# V4-AddOnZigbee-DIL-V001.net
KiCad netlist of a schematic drawn in EAGLE
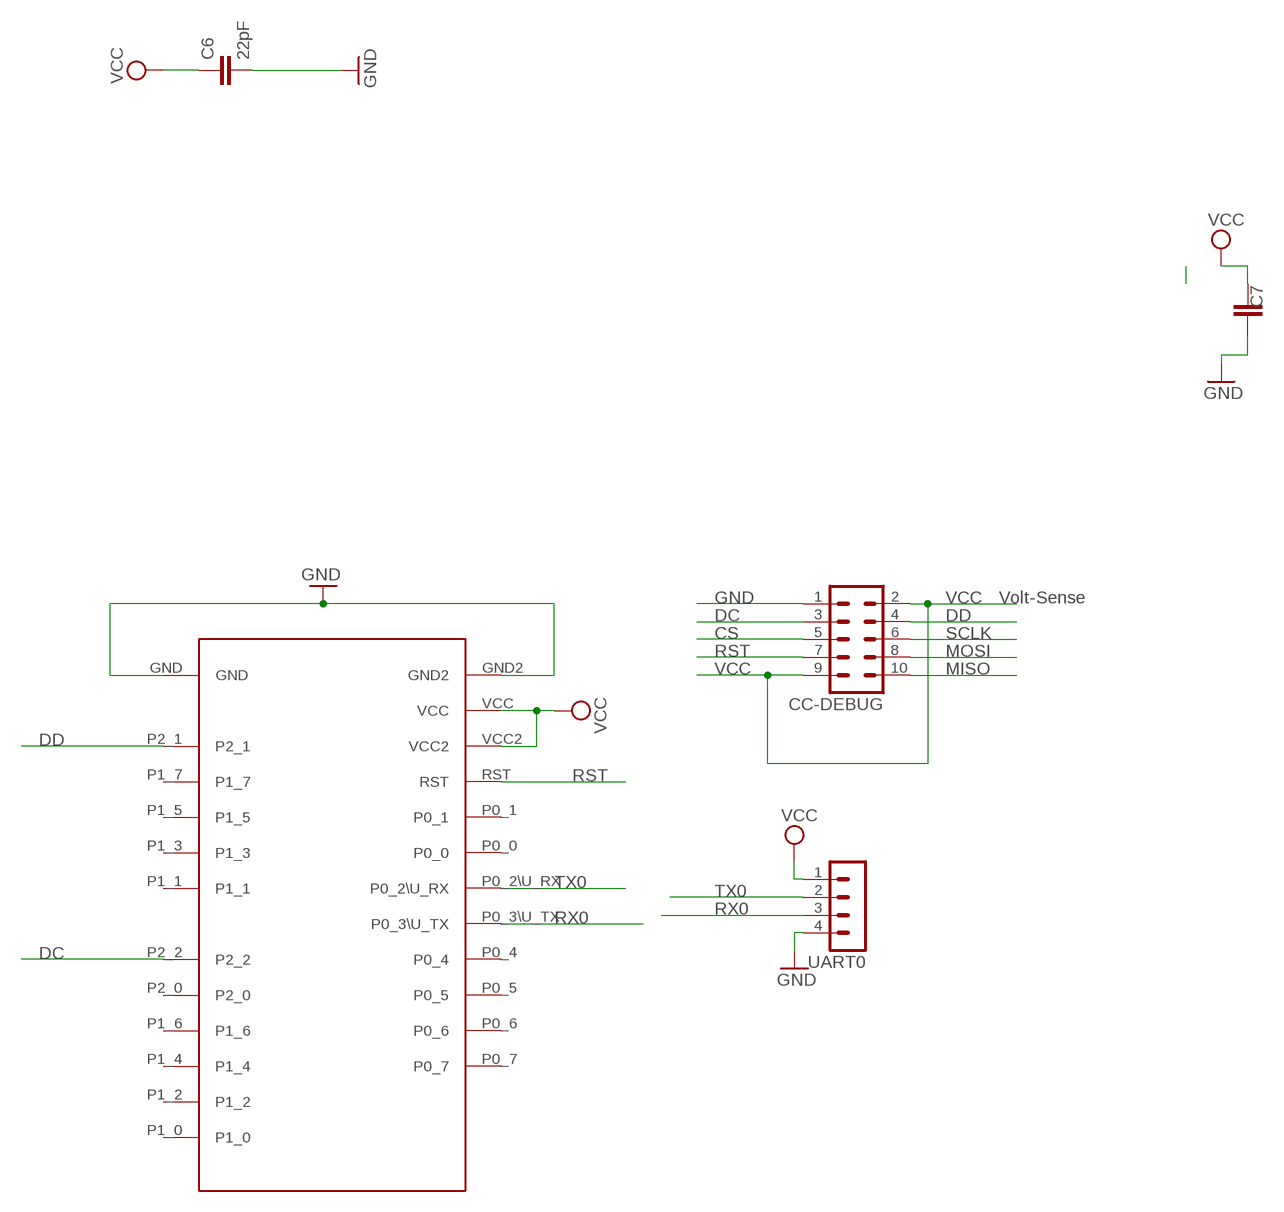
[diagram p0: schematic, sheet 1]

(export (version "E")
  (design (tool "Eeschema 10.0.6"))
  (components
    (comp (ref "C6")
      (value "22pF")
      (footprint "eagle-import:C0805")
      (libsource (lib "eagle-import") (part "C-EUC0805"))
    )
    (comp (ref "C7")
      (value "C-EUC1812")
      (footprint "eagle-import:C1812")
      (libsource (lib "eagle-import") (part "C-EUC1812"))
    )
    (comp (ref "CC-DEBUG")
      (value "MA05-2")
      (footprint "eagle-import:MA05-2")
      (libsource (lib "eagle-import") (part "MA05-2"))
    )
    (comp (ref "U$3")
      (value "CC2530_MODULE")
      (footprint "eagle-import:CC2530_DIL")
      (libsource (lib "eagle-import") (part "CC2530_MODULE"))
    )
    (comp (ref "UART0")
      (value "MA04-1")
      (footprint "eagle-import:MA04-1")
      (libsource (lib "eagle-import") (part "MA04-1"))
    )
  )
  (nets
    (net (code "1") (name "/CS") (class "Default")
      (node (ref "CC-DEBUG") (pin "5") (pinfunction "5_5") (pintype "passive"))
    )
    (net (code "2") (name "/DC") (class "Default")
      (node (ref "CC-DEBUG") (pin "3") (pinfunction "3_3") (pintype "passive"))
      (node (ref "U$3") (pin "P2_2") (pinfunction "P2_2_P2_2") (pintype "bidirectional"))
    )
    (net (code "3") (name "/DD") (class "Default")
      (node (ref "CC-DEBUG") (pin "4") (pinfunction "4_4") (pintype "passive"))
      (node (ref "U$3") (pin "P2_1") (pinfunction "P2_1_P2_1") (pintype "bidirectional"))
    )
    (net (code "4") (name "/MISO") (class "Default")
      (node (ref "CC-DEBUG") (pin "10") (pinfunction "10_10") (pintype "passive"))
    )
    (net (code "5") (name "/MOSI") (class "Default")
      (node (ref "CC-DEBUG") (pin "8") (pinfunction "8_8") (pintype "passive"))
    )
    (net (code "6") (name "/RST") (class "Default")
      (node (ref "CC-DEBUG") (pin "7") (pinfunction "7_7") (pintype "passive"))
      (node (ref "U$3") (pin "RST") (pinfunction "RST_RST") (pintype "bidirectional"))
    )
    (net (code "7") (name "/RX0") (class "Default")
      (node (ref "U$3") (pin "P0_3\\U_TX") (pinfunction "P0_3\\U_TX_P0_3\\U_TX") (pintype "bidirectional"))
      (node (ref "UART0") (pin "3") (pinfunction "3_3") (pintype "passive"))
    )
    (net (code "8") (name "/SCLK") (class "Default")
      (node (ref "CC-DEBUG") (pin "6") (pinfunction "6_6") (pintype "passive"))
    )
    (net (code "9") (name "/TX0") (class "Default")
      (node (ref "U$3") (pin "P0_2\\U_RX") (pinfunction "P0_2\\U_RX_P0_2\\U_RX") (pintype "bidirectional"))
      (node (ref "UART0") (pin "2") (pinfunction "2_2") (pintype "passive"))
    )
    (net (code "10") (name "GND") (class "Default")
      (node (ref "C6") (pin "2") (pinfunction "2_2") (pintype "passive"))
      (node (ref "C7") (pin "1") (pinfunction "1_1") (pintype "passive"))
      (node (ref "CC-DEBUG") (pin "1") (pinfunction "1_1") (pintype "passive"))
      (node (ref "U$3") (pin "GND") (pinfunction "GND_GND") (pintype "bidirectional"))
      (node (ref "U$3") (pin "GND2") (pinfunction "GND2_GND2") (pintype "bidirectional"))
      (node (ref "UART0") (pin "4") (pinfunction "4_4") (pintype "passive"))
    )
    (net (code "11") (name "VCC") (class "Default")
      (node (ref "C6") (pin "1") (pinfunction "1_1") (pintype "passive"))
      (node (ref "C7") (pin "2") (pinfunction "2_2") (pintype "passive"))
      (node (ref "CC-DEBUG") (pin "2") (pinfunction "2_2") (pintype "passive"))
      (node (ref "CC-DEBUG") (pin "9") (pinfunction "9_9") (pintype "passive"))
      (node (ref "U$3") (pin "VCC") (pinfunction "VCC_VCC") (pintype "bidirectional"))
      (node (ref "U$3") (pin "VCC2") (pinfunction "VCC2_VCC2") (pintype "bidirectional"))
      (node (ref "UART0") (pin "1") (pinfunction "1_1") (pintype "passive"))
    )
    (net (code "12") (name "unconnected-(U$3-PadP0_0)") (class "Default")
      (node (ref "U$3") (pin "P0_0") (pinfunction "P0_0_P0_0") (pintype "bidirectional"))
    )
    (net (code "13") (name "unconnected-(U$3-PadP0_1)") (class "Default")
      (node (ref "U$3") (pin "P0_1") (pinfunction "P0_1_P0_1") (pintype "bidirectional"))
    )
    (net (code "14") (name "unconnected-(U$3-PadP0_4)") (class "Default")
      (node (ref "U$3") (pin "P0_4") (pinfunction "P0_4_P0_4") (pintype "bidirectional"))
    )
    (net (code "15") (name "unconnected-(U$3-PadP0_5)") (class "Default")
      (node (ref "U$3") (pin "P0_5") (pinfunction "P0_5_P0_5") (pintype "bidirectional"))
    )
    (net (code "16") (name "unconnected-(U$3-PadP0_6)") (class "Default")
      (node (ref "U$3") (pin "P0_6") (pinfunction "P0_6_P0_6") (pintype "bidirectional"))
    )
    (net (code "17") (name "unconnected-(U$3-PadP0_7)") (class "Default")
      (node (ref "U$3") (pin "P0_7") (pinfunction "P0_7_P0_7") (pintype "bidirectional"))
    )
    (net (code "18") (name "unconnected-(U$3-PadP1_0)") (class "Default")
      (node (ref "U$3") (pin "P1_0") (pinfunction "P1_0_P1_0") (pintype "bidirectional"))
    )
    (net (code "19") (name "unconnected-(U$3-PadP1_1)") (class "Default")
      (node (ref "U$3") (pin "P1_1") (pinfunction "P1_1_P1_1") (pintype "bidirectional"))
    )
    (net (code "20") (name "unconnected-(U$3-PadP1_2)") (class "Default")
      (node (ref "U$3") (pin "P1_2") (pinfunction "P1_2_P1_2") (pintype "bidirectional"))
    )
    (net (code "21") (name "unconnected-(U$3-PadP1_3)") (class "Default")
      (node (ref "U$3") (pin "P1_3") (pinfunction "P1_3_P1_3") (pintype "bidirectional"))
    )
    (net (code "22") (name "unconnected-(U$3-PadP1_4)") (class "Default")
      (node (ref "U$3") (pin "P1_4") (pinfunction "P1_4_P1_4") (pintype "bidirectional"))
    )
    (net (code "23") (name "unconnected-(U$3-PadP1_5)") (class "Default")
      (node (ref "U$3") (pin "P1_5") (pinfunction "P1_5_P1_5") (pintype "bidirectional"))
    )
    (net (code "24") (name "unconnected-(U$3-PadP1_6)") (class "Default")
      (node (ref "U$3") (pin "P1_6") (pinfunction "P1_6_P1_6") (pintype "bidirectional"))
    )
    (net (code "25") (name "unconnected-(U$3-PadP1_7)") (class "Default")
      (node (ref "U$3") (pin "P1_7") (pinfunction "P1_7_P1_7") (pintype "bidirectional"))
    )
    (net (code "26") (name "unconnected-(U$3-PadP2_0)") (class "Default")
      (node (ref "U$3") (pin "P2_0") (pinfunction "P2_0_P2_0") (pintype "bidirectional"))
    )
  )
)
